# vssb3.net
KiCad netlist of a schematic drawn in EAGLE
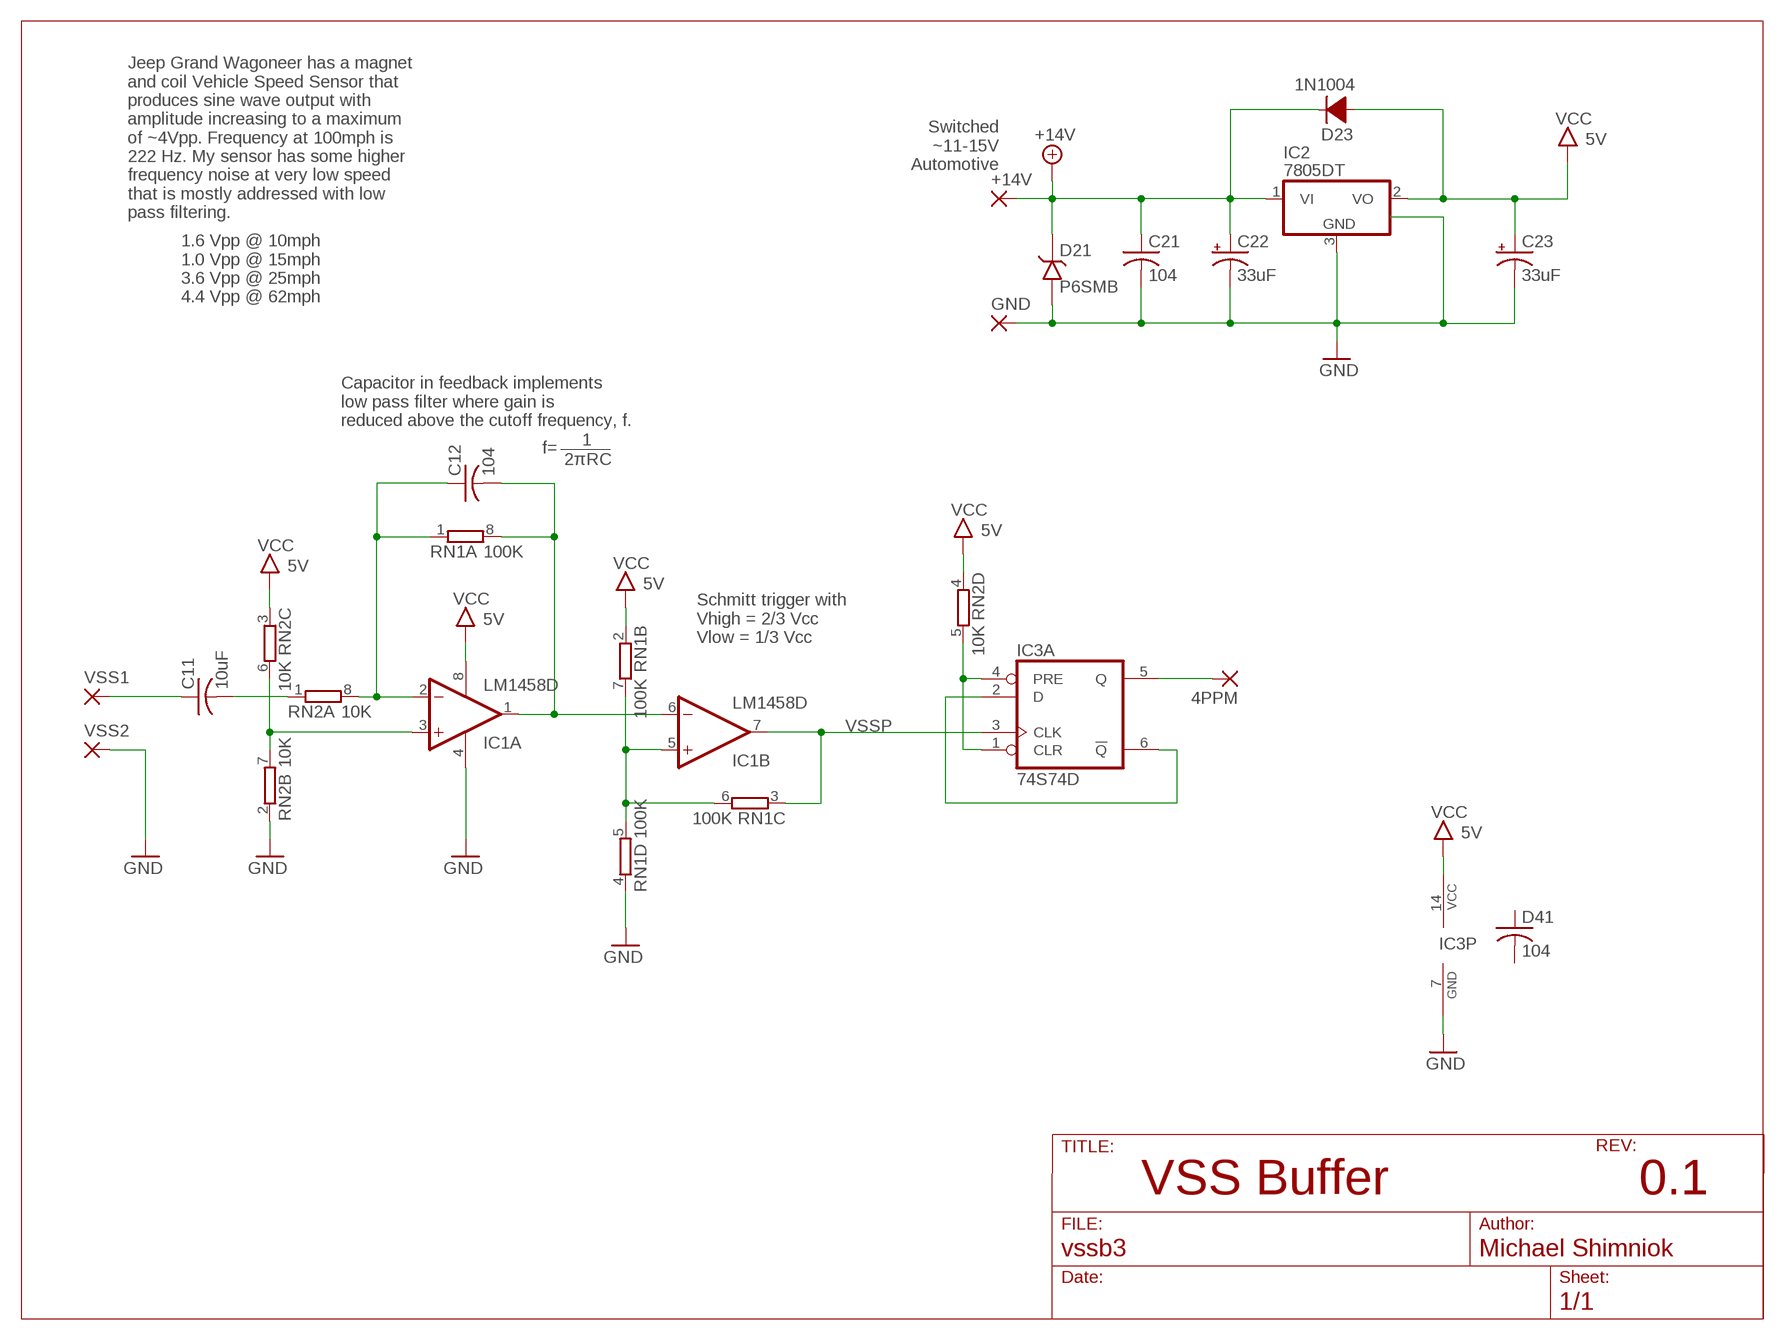
[diagram p0: schematic, sheet 1]

(export (version "E")
  (design (tool "Eeschema 10.0.6"))
  (components
    (comp (ref "+14V")
      (value "WIREPAD3,17/1,3")
      (footprint "eagle-import:3,17_1,3")
      (libsource (lib "eagle-import") (part "WIREPAD3,17/1,3"))
    )
    (comp (ref "4PPM")
      (value "WIREPAD3,17/1,3")
      (footprint "eagle-import:3,17_1,3")
      (libsource (lib "eagle-import") (part "WIREPAD3,17/1,3"))
    )
    (comp (ref "C11")
      (value "10uF")
      (footprint "eagle-import:C1206")
      (libsource (lib "eagle-import") (part "C-USC1206"))
    )
    (comp (ref "C12")
      (value "104")
      (footprint "eagle-import:C0603")
      (libsource (lib "eagle-import") (part "C-USC0603"))
    )
    (comp (ref "C21")
      (value "104")
      (footprint "eagle-import:C0603")
      (libsource (lib "eagle-import") (part "C-USC0603"))
    )
    (comp (ref "C22")
      (value "33uF")
      (footprint "eagle-import:SMC_B")
      (libsource (lib "eagle-import") (part "CPOL-USSMCB"))
    )
    (comp (ref "C23")
      (value "33uF")
      (footprint "eagle-import:SMC_B")
      (libsource (lib "eagle-import") (part "CPOL-USSMCB"))
    )
    (comp (ref "D21")
      (value "P6SMB")
      (footprint "eagle-import:DO-214AA")
      (libsource (lib "eagle-import") (part "P6SMBXXAT3GSMA"))
    )
    (comp (ref "D23")
      (value "1N1004")
      (footprint "eagle-import:SMA")
      (libsource (lib "eagle-import") (part "DIODESMA"))
    )
    (comp (ref "D41")
      (value "104")
      (footprint "eagle-import:C0603")
      (libsource (lib "eagle-import") (part "C-USC0603"))
    )
    (comp (ref "GND")
      (value "WIREPAD3,17/1,3")
      (footprint "eagle-import:3,17_1,3")
      (libsource (lib "eagle-import") (part "WIREPAD3,17/1,3"))
    )
    (comp (ref "IC1")
      (value "LM1458D")
      (footprint "eagle-import:SO08")
      (libsource (lib "eagle-import") (part "1458DLM"))
    )
    (comp (ref "IC2")
      (value "7805DT")
      (footprint "eagle-import:TO252")
      (libsource (lib "eagle-import") (part "78DT05"))
    )
    (comp (ref "IC3")
      (value "74S74D")
      (footprint "eagle-import:SO14")
      (libsource (lib "eagle-import") (part "7474DS"))
    )
    (comp (ref "RN1")
      (value "100K")
      (footprint "eagle-import:EXB38V")
      (libsource (lib "eagle-import") (part "4R-NEXB38V"))
    )
    (comp (ref "RN2")
      (value "10K")
      (footprint "eagle-import:EXB38V")
      (libsource (lib "eagle-import") (part "4R-NEXB38V"))
    )
    (comp (ref "VSS1")
      (value "WIREPAD3,17/1,3")
      (footprint "eagle-import:3,17_1,3")
      (libsource (lib "eagle-import") (part "WIREPAD3,17/1,3"))
    )
    (comp (ref "VSS2")
      (value "WIREPAD3,17/1,3")
      (footprint "eagle-import:3,17_1,3")
      (libsource (lib "eagle-import") (part "WIREPAD3,17/1,3"))
    )
  )
  (nets
    (net (code "1") (name "+14V") (class "Default")
      (node (ref "+14V") (pin "1") (pinfunction "P_1") (pintype "passive"))
      (node (ref "C21") (pin "1") (pinfunction "1_1") (pintype "passive"))
      (node (ref "C22") (pin "+") (pinfunction "+_+") (pintype "passive"))
      (node (ref "D21") (pin "P$1") (pinfunction "C_P$1") (pintype "passive"))
      (node (ref "D23") (pin "C") (pinfunction "C_C") (pintype "passive"))
      (node (ref "IC2") (pin "1") (pinfunction "VI_1") (pintype "input"))
    )
    (net (code "2") (name "/VSSP") (class "Default")
      (node (ref "IC1") (pin "7") (pinfunction "OUT_7") (pintype "output"))
      (node (ref "IC3") (pin "3") (pinfunction "CLK_3") (pintype "input"))
      (node (ref "RN1") (pin "3") (pinfunction "1_3") (pintype "passive"))
    )
    (net (code "3") (name "5V") (class "Default")
      (node (ref "C23") (pin "+") (pinfunction "+_+") (pintype "passive"))
      (node (ref "D23") (pin "A") (pinfunction "A_A") (pintype "passive"))
      (node (ref "IC1") (pin "8") (pinfunction "V+_8") (pintype "power_in"))
      (node (ref "IC2") (pin "2") (pinfunction "VO_2") (pintype "passive"))
      (node (ref "IC3") (pin "14") (pinfunction "VCC_14") (pintype "power_in"))
      (node (ref "RN1") (pin "2") (pinfunction "1_2") (pintype "passive"))
      (node (ref "RN2") (pin "3") (pinfunction "1_3") (pintype "passive"))
      (node (ref "RN2") (pin "4") (pinfunction "1_4") (pintype "passive"))
    )
    (net (code "4") (name "GND") (class "Default")
      (node (ref "C21") (pin "2") (pinfunction "2_2") (pintype "passive"))
      (node (ref "C22") (pin "-") (pinfunction "-_-") (pintype "passive"))
      (node (ref "C23") (pin "-") (pinfunction "-_-") (pintype "passive"))
      (node (ref "D21") (pin "P$2") (pinfunction "A_P$2") (pintype "passive"))
      (node (ref "GND") (pin "1") (pinfunction "P_1") (pintype "passive"))
      (node (ref "IC1") (pin "4") (pinfunction "V-_4") (pintype "power_in"))
      (node (ref "IC2") (pin "3") (pinfunction "GND_3") (pintype "passive"))
      (node (ref "IC3") (pin "7") (pinfunction "GND_7") (pintype "power_in"))
      (node (ref "RN1") (pin "4") (pinfunction "1_4") (pintype "passive"))
      (node (ref "RN2") (pin "2") (pinfunction "1_2") (pintype "passive"))
      (node (ref "VSS2") (pin "1") (pinfunction "P_1") (pintype "passive"))
    )
    (net (code "5") (name "Net-(4PPM-P)") (class "Default")
      (node (ref "4PPM") (pin "1") (pinfunction "P_1") (pintype "passive"))
      (node (ref "IC3") (pin "5") (pinfunction "Q_5") (pintype "output"))
    )
    (net (code "6") (name "Net-(C11-Pad2)") (class "Default")
      (node (ref "C11") (pin "2") (pinfunction "2_2") (pintype "passive"))
      (node (ref "RN2") (pin "1") (pinfunction "1_1") (pintype "passive"))
    )
    (net (code "7") (name "Net-(IC1A-+IN)") (class "Default")
      (node (ref "IC1") (pin "3") (pinfunction "+IN_3") (pintype "input"))
      (node (ref "RN2") (pin "6") (pinfunction "2_6") (pintype "passive"))
      (node (ref "RN2") (pin "7") (pinfunction "2_7") (pintype "passive"))
    )
    (net (code "8") (name "Net-(IC1A--IN)") (class "Default")
      (node (ref "C12") (pin "1") (pinfunction "1_1") (pintype "passive"))
      (node (ref "IC1") (pin "2") (pinfunction "-IN_2") (pintype "input"))
      (node (ref "RN1") (pin "1") (pinfunction "1_1") (pintype "passive"))
      (node (ref "RN2") (pin "8") (pinfunction "2_8") (pintype "passive"))
    )
    (net (code "9") (name "Net-(IC1A-OUT)") (class "Default")
      (node (ref "C12") (pin "2") (pinfunction "2_2") (pintype "passive"))
      (node (ref "IC1") (pin "1") (pinfunction "OUT_1") (pintype "output"))
      (node (ref "IC1") (pin "6") (pinfunction "-IN_6") (pintype "input"))
      (node (ref "RN1") (pin "8") (pinfunction "2_8") (pintype "passive"))
    )
    (net (code "10") (name "Net-(IC1B-+IN)") (class "Default")
      (node (ref "IC1") (pin "5") (pinfunction "+IN_5") (pintype "input"))
      (node (ref "RN1") (pin "5") (pinfunction "2_5") (pintype "passive"))
      (node (ref "RN1") (pin "6") (pinfunction "2_6") (pintype "passive"))
      (node (ref "RN1") (pin "7") (pinfunction "2_7") (pintype "passive"))
    )
    (net (code "11") (name "Net-(IC3A-CLR)") (class "Default")
      (node (ref "IC3") (pin "1") (pinfunction "CLR_1") (pintype "input"))
      (node (ref "IC3") (pin "4") (pinfunction "PRE_4") (pintype "input"))
      (node (ref "RN2") (pin "5") (pinfunction "2_5") (pintype "passive"))
    )
    (net (code "12") (name "Net-(IC3A-D)") (class "Default")
      (node (ref "IC3") (pin "2") (pinfunction "D_2") (pintype "input"))
      (node (ref "IC3") (pin "6") (pinfunction "~{Q}_6") (pintype "output"))
    )
    (net (code "13") (name "Net-(VSS1-P)") (class "Default")
      (node (ref "C11") (pin "1") (pinfunction "1_1") (pintype "passive"))
      (node (ref "VSS1") (pin "1") (pinfunction "P_1") (pintype "passive"))
    )
    (net (code "14") (name "unconnected-(D41-Pad1)") (class "Default")
      (node (ref "D41") (pin "1") (pinfunction "1_1") (pintype "passive"))
    )
    (net (code "15") (name "unconnected-(D41-Pad2)") (class "Default")
      (node (ref "D41") (pin "2") (pinfunction "2_2") (pintype "passive"))
    )
  )
)
